# adafruit_feather.net
KiCad netlist of a schematic drawn in Altium Designer
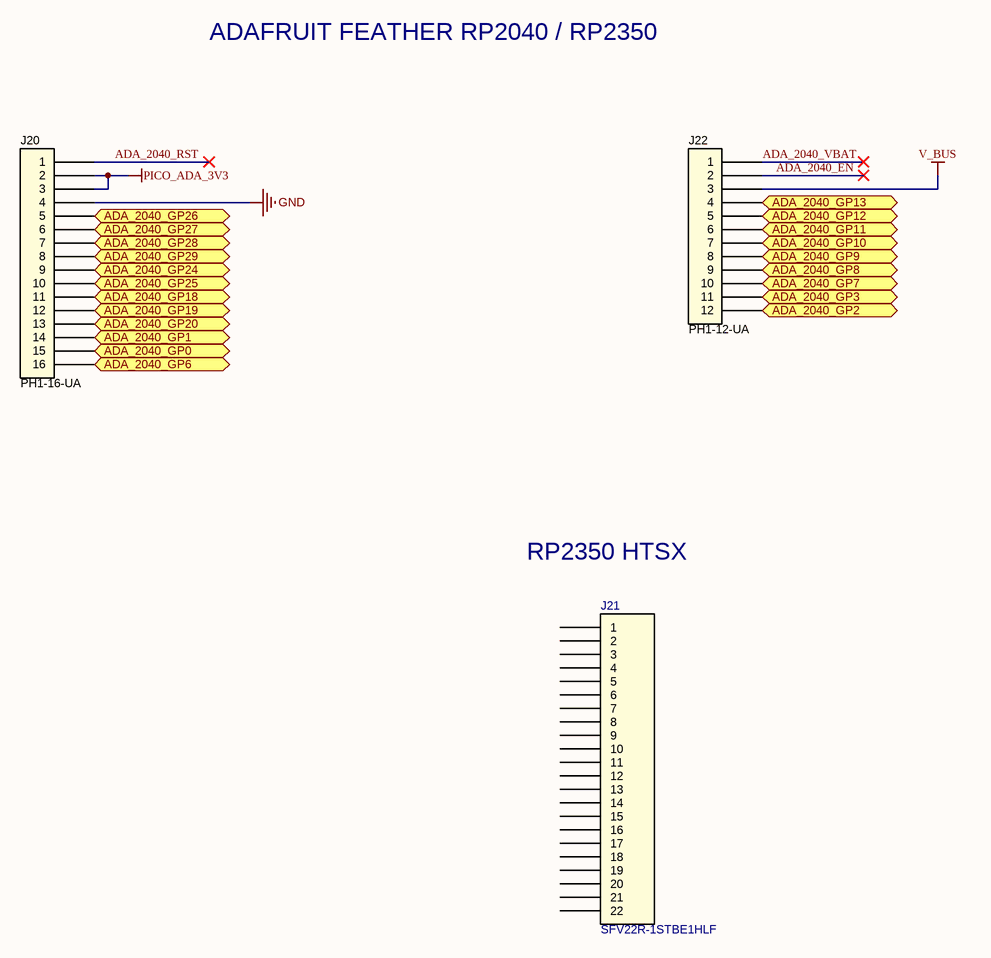
[diagram p0: adafruit_feather.SchDoc]

(export (version "E")
  (design (tool "Eeschema 10.0.6"))
  (components
    (comp (ref "J20")
      (value "PH1-16-UA")
      (footprint "CONN_ADAM_TECH_PH1-16-UA")
      (description "CONN HEADER VERT 16POS 2.54MM GOLD")
      (fields (field (name "MFR") "Adam Tech"))
      (libsource (lib "General_Library") (part "CMP-007-0080"))
    )
    (comp (ref "J21")
      (value "SFV22R-1STBE1HLF")
      (footprint "CONN_AMPHENOL_SFV22R-1STBE1HLF")
      (description "CONN FFC BOTTOM 22POS 0.5MM R/A")
      (fields (field (name "MFR") "Amphenol ICC (FCI)"))
      (libsource (lib "General_Library") (part "CMP-007-0081"))
    )
    (comp (ref "J22")
      (value "PH1-12-UA")
      (footprint "CONN_ADAM_TECH_PH1-12-UA")
      (description "CONN HEADER VERT 12POS 2.54MM GOLD")
      (fields (field (name "MFR") "Adam Tech"))
      (libsource (lib "General_Library") (part "CMP-007-0079"))
    )
  )
  (nets
    (net (code "1") (name "/ADA_2040_EN") (class "Default")
      (node (ref "J22") (pin "2") (pinfunction "2_2") (pintype "passive+no_connect"))
    )
    (net (code "2") (name "/ADA_2040_GP0") (class "Default")
      (node (ref "J20") (pin "15") (pinfunction "15_15") (pintype "passive"))
    )
    (net (code "3") (name "/ADA_2040_GP1") (class "Default")
      (node (ref "J20") (pin "14") (pinfunction "14_14") (pintype "passive"))
    )
    (net (code "4") (name "/ADA_2040_GP2") (class "Default")
      (node (ref "J22") (pin "12") (pinfunction "12_12") (pintype "passive"))
    )
    (net (code "5") (name "/ADA_2040_GP3") (class "Default")
      (node (ref "J22") (pin "11") (pinfunction "11_11") (pintype "passive"))
    )
    (net (code "6") (name "/ADA_2040_GP6") (class "Default")
      (node (ref "J20") (pin "16") (pinfunction "16_16") (pintype "passive"))
    )
    (net (code "7") (name "/ADA_2040_GP7") (class "Default")
      (node (ref "J22") (pin "10") (pinfunction "10_10") (pintype "passive"))
    )
    (net (code "8") (name "/ADA_2040_GP8") (class "Default")
      (node (ref "J22") (pin "9") (pinfunction "9_9") (pintype "passive"))
    )
    (net (code "9") (name "/ADA_2040_GP9") (class "Default")
      (node (ref "J22") (pin "8") (pinfunction "8_8") (pintype "passive"))
    )
    (net (code "10") (name "/ADA_2040_GP10") (class "Default")
      (node (ref "J22") (pin "7") (pinfunction "7_7") (pintype "passive"))
    )
    (net (code "11") (name "/ADA_2040_GP11") (class "Default")
      (node (ref "J22") (pin "6") (pinfunction "6_6") (pintype "passive"))
    )
    (net (code "12") (name "/ADA_2040_GP12") (class "Default")
      (node (ref "J22") (pin "5") (pinfunction "5_5") (pintype "passive"))
    )
    (net (code "13") (name "/ADA_2040_GP13") (class "Default")
      (node (ref "J22") (pin "4") (pinfunction "4_4") (pintype "passive"))
    )
    (net (code "14") (name "/ADA_2040_GP18") (class "Default")
      (node (ref "J20") (pin "11") (pinfunction "11_11") (pintype "passive"))
    )
    (net (code "15") (name "/ADA_2040_GP19") (class "Default")
      (node (ref "J20") (pin "12") (pinfunction "12_12") (pintype "passive"))
    )
    (net (code "16") (name "/ADA_2040_GP20") (class "Default")
      (node (ref "J20") (pin "13") (pinfunction "13_13") (pintype "passive"))
    )
    (net (code "17") (name "/ADA_2040_GP24") (class "Default")
      (node (ref "J20") (pin "9") (pinfunction "9_9") (pintype "passive"))
    )
    (net (code "18") (name "/ADA_2040_GP25") (class "Default")
      (node (ref "J20") (pin "10") (pinfunction "10_10") (pintype "passive"))
    )
    (net (code "19") (name "/ADA_2040_GP26") (class "Default")
      (node (ref "J20") (pin "5") (pinfunction "5_5") (pintype "passive"))
    )
    (net (code "20") (name "/ADA_2040_GP27") (class "Default")
      (node (ref "J20") (pin "6") (pinfunction "6_6") (pintype "passive"))
    )
    (net (code "21") (name "/ADA_2040_GP28") (class "Default")
      (node (ref "J20") (pin "7") (pinfunction "7_7") (pintype "passive"))
    )
    (net (code "22") (name "/ADA_2040_GP29") (class "Default")
      (node (ref "J20") (pin "8") (pinfunction "8_8") (pintype "passive"))
    )
    (net (code "23") (name "/ADA_2040_RST") (class "Default")
      (node (ref "J20") (pin "1") (pinfunction "1_1") (pintype "passive+no_connect"))
    )
    (net (code "24") (name "/ADA_2040_VBAT") (class "Default")
      (node (ref "J22") (pin "1") (pinfunction "1_1") (pintype "passive+no_connect"))
    )
    (net (code "25") (name "GND") (class "Default")
      (node (ref "J20") (pin "4") (pinfunction "4_4") (pintype "passive"))
    )
    (net (code "26") (name "PICO_ADA_3V3") (class "Default")
      (node (ref "J20") (pin "2") (pinfunction "2_2") (pintype "passive"))
      (node (ref "J20") (pin "3") (pinfunction "3_3") (pintype "passive"))
    )
    (net (code "27") (name "V_BUS") (class "Default")
      (node (ref "J22") (pin "3") (pinfunction "3_3") (pintype "passive"))
    )
    (net (code "28") (name "unconnected-(J21-Pad1)") (class "Default")
      (node (ref "J21") (pin "1") (pinfunction "1_1") (pintype "power_in"))
    )
    (net (code "29") (name "unconnected-(J21-Pad2)") (class "Default")
      (node (ref "J21") (pin "2") (pinfunction "2_2") (pintype "power_in"))
    )
    (net (code "30") (name "unconnected-(J21-Pad3)") (class "Default")
      (node (ref "J21") (pin "3") (pinfunction "3_3") (pintype "power_in"))
    )
    (net (code "31") (name "unconnected-(J21-Pad4)") (class "Default")
      (node (ref "J21") (pin "4") (pinfunction "4_4") (pintype "power_in"))
    )
    (net (code "32") (name "unconnected-(J21-Pad5)") (class "Default")
      (node (ref "J21") (pin "5") (pinfunction "5_5") (pintype "power_in"))
    )
    (net (code "33") (name "unconnected-(J21-Pad6)") (class "Default")
      (node (ref "J21") (pin "6") (pinfunction "6_6") (pintype "power_in"))
    )
    (net (code "34") (name "unconnected-(J21-Pad7)") (class "Default")
      (node (ref "J21") (pin "7") (pinfunction "7_7") (pintype "power_in"))
    )
    (net (code "35") (name "unconnected-(J21-Pad8)") (class "Default")
      (node (ref "J21") (pin "8") (pinfunction "8_8") (pintype "power_in"))
    )
    (net (code "36") (name "unconnected-(J21-Pad9)") (class "Default")
      (node (ref "J21") (pin "9") (pinfunction "9_9") (pintype "power_in"))
    )
    (net (code "37") (name "unconnected-(J21-Pad10)") (class "Default")
      (node (ref "J21") (pin "10") (pinfunction "10_10") (pintype "power_in"))
    )
    (net (code "38") (name "unconnected-(J21-Pad11)") (class "Default")
      (node (ref "J21") (pin "11") (pinfunction "11_11") (pintype "power_in"))
    )
    (net (code "39") (name "unconnected-(J21-Pad12)") (class "Default")
      (node (ref "J21") (pin "12") (pinfunction "12_12") (pintype "power_in"))
    )
    (net (code "40") (name "unconnected-(J21-Pad13)") (class "Default")
      (node (ref "J21") (pin "13") (pinfunction "13_13") (pintype "power_in"))
    )
    (net (code "41") (name "unconnected-(J21-Pad14)") (class "Default")
      (node (ref "J21") (pin "14") (pinfunction "14_14") (pintype "power_in"))
    )
    (net (code "42") (name "unconnected-(J21-Pad15)") (class "Default")
      (node (ref "J21") (pin "15") (pinfunction "15_15") (pintype "power_in"))
    )
    (net (code "43") (name "unconnected-(J21-Pad16)") (class "Default")
      (node (ref "J21") (pin "16") (pinfunction "16_16") (pintype "power_in"))
    )
    (net (code "44") (name "unconnected-(J21-Pad17)") (class "Default")
      (node (ref "J21") (pin "17") (pinfunction "17_17") (pintype "power_in"))
    )
    (net (code "45") (name "unconnected-(J21-Pad18)") (class "Default")
      (node (ref "J21") (pin "18") (pinfunction "18_18") (pintype "power_in"))
    )
    (net (code "46") (name "unconnected-(J21-Pad19)") (class "Default")
      (node (ref "J21") (pin "19") (pinfunction "19_19") (pintype "power_in"))
    )
    (net (code "47") (name "unconnected-(J21-Pad20)") (class "Default")
      (node (ref "J21") (pin "20") (pinfunction "20_20") (pintype "power_in"))
    )
    (net (code "48") (name "unconnected-(J21-Pad21)") (class "Default")
      (node (ref "J21") (pin "21") (pinfunction "21_21") (pintype "power_in"))
    )
    (net (code "49") (name "unconnected-(J21-Pad22)") (class "Default")
      (node (ref "J21") (pin "22") (pinfunction "22_22") (pintype "power_in"))
    )
  )
)
